# ANDOR4.net
KiCad netlist of a schematic drawn in Altium Designer
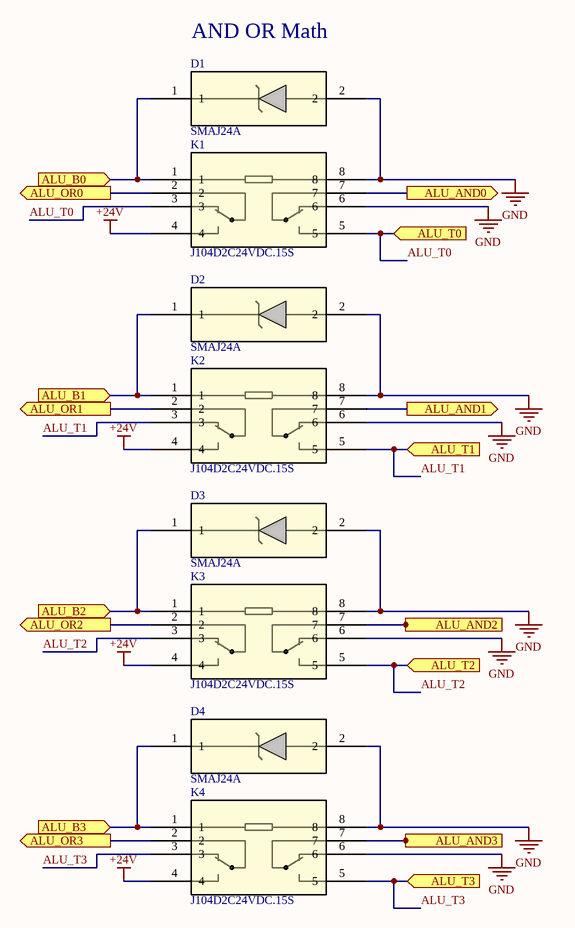
[diagram p0: ANDOR4.SchDoc]

(export (version "E")
  (design (tool "Eeschema 10.0.6"))
  (components
    (comp (ref "D1")
      (value "SMAJ24A")
      (footprint "DI SMAJ24A")
      (description "SMAJ Series 400 W 24 V Uni-Directional Surface Mount TVS Diode - DO-214AC")
      (fields (field (name "MANUFACTURER") "Littelfuse"))
      (libsource (lib "Schlib1") (part "DI SMAJ24A"))
    )
    (comp (ref "D2")
      (value "SMAJ24A")
      (footprint "DI SMAJ24A")
      (description "SMAJ Series 400 W 24 V Uni-Directional Surface Mount TVS Diode - DO-214AC")
      (fields (field (name "MANUFACTURER") "Littelfuse"))
      (libsource (lib "Schlib1") (part "DI SMAJ24A"))
    )
    (comp (ref "D3")
      (value "SMAJ24A")
      (footprint "DI SMAJ24A")
      (description "SMAJ Series 400 W 24 V Uni-Directional Surface Mount TVS Diode - DO-214AC")
      (fields (field (name "MANUFACTURER") "Littelfuse"))
      (libsource (lib "Schlib1") (part "DI SMAJ24A"))
    )
    (comp (ref "D4")
      (value "SMAJ24A")
      (footprint "DI SMAJ24A")
      (description "SMAJ Series 400 W 24 V Uni-Directional Surface Mount TVS Diode - DO-214AC")
      (fields (field (name "MANUFACTURER") "Littelfuse"))
      (libsource (lib "Schlib1") (part "DI SMAJ24A"))
    )
    (comp (ref "K1")
      (value "J104D2C24VDC.15S")
      (footprint "Relay J104D2C24VDC.15S")
      (description "Relay Ul Gen Purp DPDT 2C 24VDC")
      (fields (field (name "MANUFACTURER") "CIT Relay & Switch"))
      (libsource (lib "Schlib1") (part "Relay J104D2C24VDC.15S"))
    )
    (comp (ref "K2")
      (value "J104D2C24VDC.15S")
      (footprint "Relay J104D2C24VDC.15S")
      (description "Relay Ul Gen Purp DPDT 2C 24VDC")
      (fields (field (name "MANUFACTURER") "CIT Relay & Switch"))
      (libsource (lib "Schlib1") (part "Relay J104D2C24VDC.15S"))
    )
    (comp (ref "K3")
      (value "J104D2C24VDC.15S")
      (footprint "Relay J104D2C24VDC.15S")
      (description "Relay Ul Gen Purp DPDT 2C 24VDC")
      (fields (field (name "MANUFACTURER") "CIT Relay & Switch"))
      (libsource (lib "Schlib1") (part "Relay J104D2C24VDC.15S"))
    )
    (comp (ref "K4")
      (value "J104D2C24VDC.15S")
      (footprint "Relay J104D2C24VDC.15S")
      (description "Relay Ul Gen Purp DPDT 2C 24VDC")
      (fields (field (name "MANUFACTURER") "CIT Relay & Switch"))
      (libsource (lib "Schlib1") (part "Relay J104D2C24VDC.15S"))
    )
  )
  (nets
    (net (code "1") (name "+24V") (class "Default")
      (node (ref "K1") (pin "4") (pinfunction "4_4") (pintype "passive"))
      (node (ref "K2") (pin "4") (pinfunction "4_4") (pintype "passive"))
      (node (ref "K3") (pin "4") (pinfunction "4_4") (pintype "passive"))
      (node (ref "K4") (pin "4") (pinfunction "4_4") (pintype "passive"))
    )
    (net (code "2") (name "/ALU_AND0") (class "Default")
      (node (ref "K1") (pin "7") (pinfunction "7_7") (pintype "passive"))
    )
    (net (code "3") (name "/ALU_AND1") (class "Default")
      (node (ref "K2") (pin "7") (pinfunction "7_7") (pintype "passive"))
    )
    (net (code "4") (name "/ALU_AND2") (class "Default")
      (node (ref "K3") (pin "7") (pinfunction "7_7") (pintype "passive"))
    )
    (net (code "5") (name "/ALU_AND3") (class "Default")
      (node (ref "K4") (pin "7") (pinfunction "7_7") (pintype "passive"))
    )
    (net (code "6") (name "/ALU_B0") (class "Default")
      (node (ref "D1") (pin "1") (pinfunction "1_1") (pintype "passive"))
      (node (ref "K1") (pin "1") (pinfunction "1_1") (pintype "passive"))
    )
    (net (code "7") (name "/ALU_B1") (class "Default")
      (node (ref "D2") (pin "1") (pinfunction "1_1") (pintype "passive"))
      (node (ref "K2") (pin "1") (pinfunction "1_1") (pintype "passive"))
    )
    (net (code "8") (name "/ALU_B2") (class "Default")
      (node (ref "D3") (pin "1") (pinfunction "1_1") (pintype "passive"))
      (node (ref "K3") (pin "1") (pinfunction "1_1") (pintype "passive"))
    )
    (net (code "9") (name "/ALU_B3") (class "Default")
      (node (ref "D4") (pin "1") (pinfunction "1_1") (pintype "passive"))
      (node (ref "K4") (pin "1") (pinfunction "1_1") (pintype "passive"))
    )
    (net (code "10") (name "/ALU_OR0") (class "Default")
      (node (ref "K1") (pin "2") (pinfunction "2_2") (pintype "passive"))
    )
    (net (code "11") (name "/ALU_OR1") (class "Default")
      (node (ref "K2") (pin "2") (pinfunction "2_2") (pintype "passive"))
    )
    (net (code "12") (name "/ALU_OR2") (class "Default")
      (node (ref "K3") (pin "2") (pinfunction "2_2") (pintype "passive"))
    )
    (net (code "13") (name "/ALU_OR3") (class "Default")
      (node (ref "K4") (pin "2") (pinfunction "2_2") (pintype "passive"))
    )
    (net (code "14") (name "/ALU_T0") (class "Default")
      (node (ref "K1") (pin "3") (pinfunction "3_3") (pintype "passive"))
      (node (ref "K1") (pin "5") (pinfunction "5_5") (pintype "passive"))
    )
    (net (code "15") (name "/ALU_T1") (class "Default")
      (node (ref "K2") (pin "3") (pinfunction "3_3") (pintype "passive"))
      (node (ref "K2") (pin "5") (pinfunction "5_5") (pintype "passive"))
    )
    (net (code "16") (name "/ALU_T2") (class "Default")
      (node (ref "K3") (pin "3") (pinfunction "3_3") (pintype "passive"))
      (node (ref "K3") (pin "5") (pinfunction "5_5") (pintype "passive"))
    )
    (net (code "17") (name "/ALU_T3") (class "Default")
      (node (ref "K4") (pin "3") (pinfunction "3_3") (pintype "passive"))
      (node (ref "K4") (pin "5") (pinfunction "5_5") (pintype "passive"))
    )
    (net (code "18") (name "GND") (class "Default")
      (node (ref "D1") (pin "2") (pinfunction "2_2") (pintype "passive"))
      (node (ref "D2") (pin "2") (pinfunction "2_2") (pintype "passive"))
      (node (ref "D3") (pin "2") (pinfunction "2_2") (pintype "passive"))
      (node (ref "D4") (pin "2") (pinfunction "2_2") (pintype "passive"))
      (node (ref "K1") (pin "6") (pinfunction "6_6") (pintype "passive"))
      (node (ref "K1") (pin "8") (pinfunction "8_8") (pintype "passive"))
      (node (ref "K2") (pin "6") (pinfunction "6_6") (pintype "passive"))
      (node (ref "K2") (pin "8") (pinfunction "8_8") (pintype "passive"))
      (node (ref "K3") (pin "6") (pinfunction "6_6") (pintype "passive"))
      (node (ref "K3") (pin "8") (pinfunction "8_8") (pintype "passive"))
      (node (ref "K4") (pin "6") (pinfunction "6_6") (pintype "passive"))
      (node (ref "K4") (pin "8") (pinfunction "8_8") (pintype "passive"))
    )
  )
)
